# CLK_INPUT.net
KiCad netlist of a schematic drawn in Altium Designer
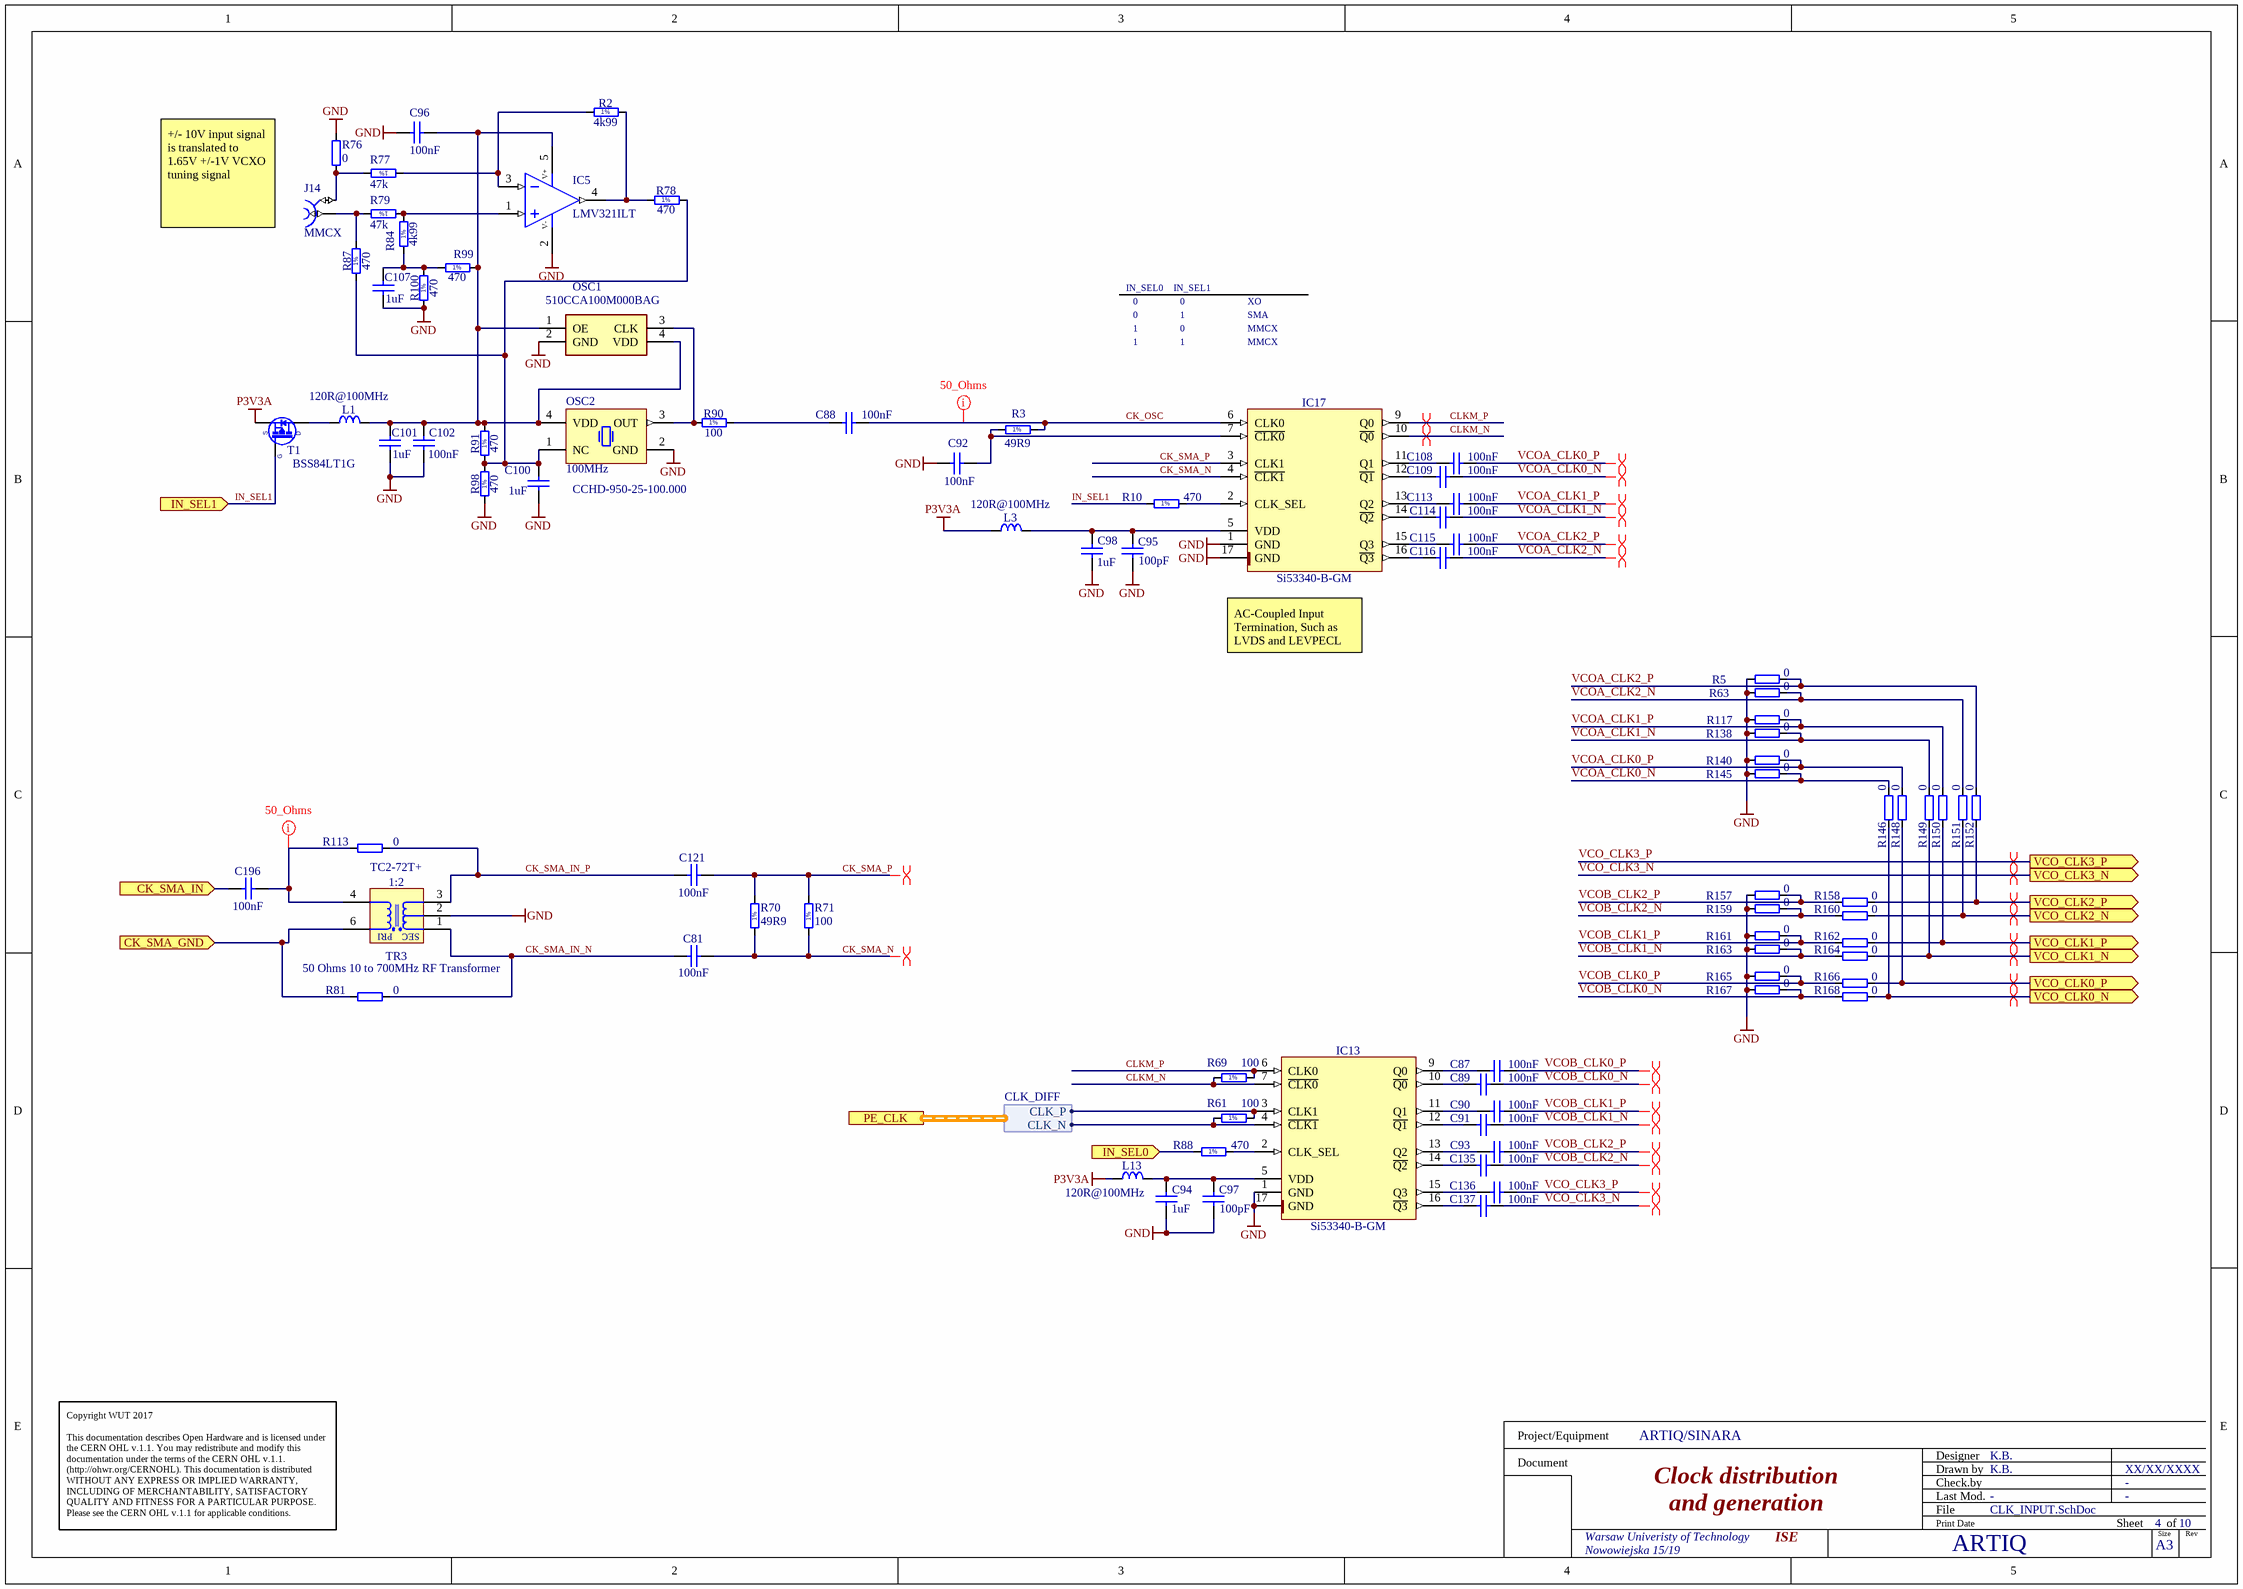
[diagram p0: CLK_INPUT.SchDoc]

(export (version "E")
  (design (tool "Eeschema 10.0.6"))
  (components
    (comp (ref "C81")
      (value "100nF")
      (footprint "CAPC1005X55N")
      (description "Non-polarised capacitor")
      (fields
        (field (name "PART NUMBER") "CC0402_100NF_16V_10%_X5R")
        (field (name "VOLTAGE") "16V")
        (field (name "AUTHOR") "CERN DEM JLC")
      )
      (libsource (lib "Capacitors") (part "Capacitor - non polarized"))
    )
    (comp (ref "C87")
      (value "100nF")
      (footprint "CAPC1005X55N")
      (description "Non-polarised capacitor")
      (fields
        (field (name "PART NUMBER") "CC0402_100NF_16V_10%_X5R")
        (field (name "VOLTAGE") "16V")
        (field (name "AUTHOR") "CERN DEM JLC")
      )
      (libsource (lib "Capacitors") (part "Capacitor - non polarized"))
    )
    (comp (ref "C88")
      (value "100nF")
      (footprint "CAPC1005X55N")
      (description "Non-polarised capacitor")
      (fields
        (field (name "PART NUMBER") "CC0402_100NF_16V_10%_X5R")
        (field (name "VOLTAGE") "16V")
        (field (name "AUTHOR") "CERN DEM JLC")
      )
      (libsource (lib "Capacitors") (part "Capacitor - non polarized"))
    )
    (comp (ref "C89")
      (value "100nF")
      (footprint "CAPC1005X55N")
      (description "Non-polarised capacitor")
      (fields
        (field (name "PART NUMBER") "CC0402_100NF_16V_10%_X5R")
        (field (name "VOLTAGE") "16V")
        (field (name "AUTHOR") "CERN DEM JLC")
      )
      (libsource (lib "Capacitors") (part "Capacitor - non polarized"))
    )
    (comp (ref "C90")
      (value "100nF")
      (footprint "CAPC1005X55N")
      (description "Non-polarised capacitor")
      (fields
        (field (name "PART NUMBER") "CC0402_100NF_16V_10%_X5R")
        (field (name "VOLTAGE") "16V")
        (field (name "AUTHOR") "CERN DEM JLC")
      )
      (libsource (lib "Capacitors") (part "Capacitor - non polarized"))
    )
    (comp (ref "C91")
      (value "100nF")
      (footprint "CAPC1005X55N")
      (description "Non-polarised capacitor")
      (fields
        (field (name "PART NUMBER") "CC0402_100NF_16V_10%_X5R")
        (field (name "VOLTAGE") "16V")
        (field (name "AUTHOR") "CERN DEM JLC")
      )
      (libsource (lib "Capacitors") (part "Capacitor - non polarized"))
    )
    (comp (ref "C92")
      (value "100nF")
      (footprint "CAPC1005X55N")
      (description "Non-polarised capacitor")
      (fields
        (field (name "PART NUMBER") "CC0402_100NF_16V_10%_X5R")
        (field (name "VOLTAGE") "16V")
        (field (name "AUTHOR") "CERN DEM JLC")
      )
      (libsource (lib "Capacitors") (part "Capacitor - non polarized"))
    )
    (comp (ref "C93")
      (value "100nF")
      (footprint "CAPC1005X55N")
      (description "Non-polarised capacitor")
      (fields
        (field (name "PART NUMBER") "CC0402_100NF_16V_10%_X5R")
        (field (name "VOLTAGE") "16V")
        (field (name "AUTHOR") "CERN DEM JLC")
      )
      (libsource (lib "Capacitors") (part "Capacitor - non polarized"))
    )
    (comp (ref "C94")
      (value "1uF")
      (footprint "CAPC1005X55N")
      (description "Non-polarised capacitor")
      (fields
        (field (name "PART NUMBER") "CC0402_1UF_16V_10%_X5R")
        (field (name "VOLTAGE") "16V")
        (field (name "AUTHOR") "CERN DEM JLC")
      )
      (libsource (lib "Capacitors") (part "Capacitor - non polarized"))
    )
    (comp (ref "C95")
      (value "100pF")
      (footprint "CAPC1005X55N")
      (description "Non-polarised capacitor")
      (fields
        (field (name "PART NUMBER") "CC0402_100PF_50V_5%_C0G")
        (field (name "VOLTAGE") "50V")
        (field (name "AUTHOR") "CERN DEM JLC")
      )
      (libsource (lib "Capacitors") (part "Capacitor - non polarized"))
    )
    (comp (ref "C96")
      (value "100nF")
      (footprint "CAPC1005X55N")
      (description "Non-polarised capacitor")
      (fields
        (field (name "PART NUMBER") "CC0402_100NF_16V_10%_X5R")
        (field (name "VOLTAGE") "16V")
        (field (name "AUTHOR") "CERN DEM JLC")
      )
      (libsource (lib "Capacitors") (part "Capacitor - non polarized"))
    )
    (comp (ref "C97")
      (value "100pF")
      (footprint "CAPC1005X55N")
      (description "Non-polarised capacitor")
      (fields
        (field (name "PART NUMBER") "CC0402_100PF_50V_5%_C0G")
        (field (name "VOLTAGE") "50V")
        (field (name "AUTHOR") "CERN DEM JLC")
      )
      (libsource (lib "Capacitors") (part "Capacitor - non polarized"))
    )
    (comp (ref "C98")
      (value "1uF")
      (footprint "CAPC1005X55N")
      (description "Non-polarised capacitor")
      (fields
        (field (name "PART NUMBER") "CC0402_1UF_16V_10%_X5R")
        (field (name "VOLTAGE") "16V")
        (field (name "AUTHOR") "CERN DEM JLC")
      )
      (libsource (lib "Capacitors") (part "Capacitor - non polarized"))
    )
    (comp (ref "C100")
      (value "1uF")
      (footprint "CAPC1005X55N")
      (description "Non-polarised capacitor")
      (fields
        (field (name "PART NUMBER") "CC0402_1UF_16V_10%_X5R")
        (field (name "VOLTAGE") "16V")
        (field (name "AUTHOR") "CERN DEM JLC")
      )
      (libsource (lib "Capacitors") (part "Capacitor - non polarized"))
    )
    (comp (ref "C101")
      (value "1uF")
      (footprint "CAPC1005X55N")
      (description "Non-polarised capacitor")
      (fields
        (field (name "PART NUMBER") "CC0402_1UF_16V_10%_X5R")
        (field (name "VOLTAGE") "16V")
        (field (name "AUTHOR") "CERN DEM JLC")
      )
      (libsource (lib "Capacitors") (part "Capacitor - non polarized"))
    )
    (comp (ref "C102")
      (value "100nF")
      (footprint "CAPC1005X55N")
      (description "Non-polarised capacitor")
      (fields
        (field (name "PART NUMBER") "CC0402_100NF_16V_10%_X5R")
        (field (name "VOLTAGE") "16V")
        (field (name "AUTHOR") "CERN DEM JLC")
      )
      (libsource (lib "Capacitors") (part "Capacitor - non polarized"))
    )
    (comp (ref "C107")
      (value "1uF")
      (footprint "CAPC1005X55N")
      (description "Non-polarised capacitor")
      (fields
        (field (name "PART NUMBER") "CC0402_1UF_16V_10%_X5R")
        (field (name "VOLTAGE") "16V")
        (field (name "AUTHOR") "CERN DEM JLC")
      )
      (libsource (lib "Capacitors") (part "Capacitor - non polarized"))
    )
    (comp (ref "C108")
      (value "100nF")
      (footprint "CAPC1005X55N")
      (description "Non-polarised capacitor")
      (fields
        (field (name "PART NUMBER") "CC0402_100NF_16V_10%_X5R")
        (field (name "VOLTAGE") "16V")
        (field (name "AUTHOR") "CERN DEM JLC")
      )
      (libsource (lib "Capacitors") (part "Capacitor - non polarized"))
    )
    (comp (ref "C109")
      (value "100nF")
      (footprint "CAPC1005X55N")
      (description "Non-polarised capacitor")
      (fields
        (field (name "PART NUMBER") "CC0402_100NF_16V_10%_X5R")
        (field (name "VOLTAGE") "16V")
        (field (name "AUTHOR") "CERN DEM JLC")
      )
      (libsource (lib "Capacitors") (part "Capacitor - non polarized"))
    )
    (comp (ref "C113")
      (value "100nF")
      (footprint "CAPC1005X55N")
      (description "Non-polarised capacitor")
      (fields
        (field (name "PART NUMBER") "CC0402_100NF_16V_10%_X5R")
        (field (name "VOLTAGE") "16V")
        (field (name "AUTHOR") "CERN DEM JLC")
      )
      (libsource (lib "Capacitors") (part "Capacitor - non polarized"))
    )
    (comp (ref "C114")
      (value "100nF")
      (footprint "CAPC1005X55N")
      (description "Non-polarised capacitor")
      (fields
        (field (name "PART NUMBER") "CC0402_100NF_16V_10%_X5R")
        (field (name "VOLTAGE") "16V")
        (field (name "AUTHOR") "CERN DEM JLC")
      )
      (libsource (lib "Capacitors") (part "Capacitor - non polarized"))
    )
    (comp (ref "C115")
      (value "100nF")
      (footprint "CAPC1005X55N")
      (description "Non-polarised capacitor")
      (fields
        (field (name "PART NUMBER") "CC0402_100NF_16V_10%_X5R")
        (field (name "VOLTAGE") "16V")
        (field (name "AUTHOR") "CERN DEM JLC")
      )
      (libsource (lib "Capacitors") (part "Capacitor - non polarized"))
    )
    (comp (ref "C116")
      (value "100nF")
      (footprint "CAPC1005X55N")
      (description "Non-polarised capacitor")
      (fields
        (field (name "PART NUMBER") "CC0402_100NF_16V_10%_X5R")
        (field (name "VOLTAGE") "16V")
        (field (name "AUTHOR") "CERN DEM JLC")
      )
      (libsource (lib "Capacitors") (part "Capacitor - non polarized"))
    )
    (comp (ref "C121")
      (value "100nF")
      (footprint "CAPC1005X55N")
      (description "Non-polarised capacitor")
      (fields
        (field (name "PART NUMBER") "CC0402_100NF_16V_10%_X5R")
        (field (name "VOLTAGE") "16V")
        (field (name "AUTHOR") "CERN DEM JLC")
      )
      (libsource (lib "Capacitors") (part "Capacitor - non polarized"))
    )
    (comp (ref "C135")
      (value "100nF")
      (footprint "CAPC1005X55N")
      (description "Non-polarised capacitor")
      (fields
        (field (name "PART NUMBER") "CC0402_100NF_16V_10%_X5R")
        (field (name "VOLTAGE") "16V")
        (field (name "AUTHOR") "CERN DEM JLC")
      )
      (libsource (lib "Capacitors") (part "Capacitor - non polarized"))
    )
    (comp (ref "C136")
      (value "100nF")
      (footprint "CAPC1005X55N")
      (description "Non-polarised capacitor")
      (fields
        (field (name "PART NUMBER") "CC0402_100NF_16V_10%_X5R")
        (field (name "VOLTAGE") "16V")
        (field (name "AUTHOR") "CERN DEM JLC")
      )
      (libsource (lib "Capacitors") (part "Capacitor - non polarized"))
    )
    (comp (ref "C137")
      (value "100nF")
      (footprint "CAPC1005X55N")
      (description "Non-polarised capacitor")
      (fields
        (field (name "PART NUMBER") "CC0402_100NF_16V_10%_X5R")
        (field (name "VOLTAGE") "16V")
        (field (name "AUTHOR") "CERN DEM JLC")
      )
      (libsource (lib "Capacitors") (part "Capacitor - non polarized"))
    )
    (comp (ref "C196")
      (value "100nF")
      (footprint "CAPC1005X55N")
      (description "Non-polarised capacitor")
      (fields
        (field (name "PART NUMBER") "CC0402_100NF_16V_10%_X5R")
        (field (name "VOLTAGE") "16V")
        (field (name "AUTHOR") "CERN DEM JLC")
      )
      (libsource (lib "Capacitors") (part "Capacitor - non polarized"))
    )
    (comp (ref "IC5")
      (value "LMV321ILT")
      (footprint "SOT95P280X145-5N")
      (description "Operational Amplifier")
      (fields (field (name "MANUFACTURER") "ST MICROELECTRONICS") (field (name "AUTHOR") "CERN DEM MR"))
      (libsource (lib "ICs And Semiconductors") (part "Operational Amplifier Type10"))
    )
    (comp (ref "IC13")
      (value "Si53340-B-GM")
      (footprint "QFN50P300X300X90-17N-S175")
      (description "Low-Jitter LVDS Fanout Clock Buffers, 10-Output,  Any-Input, Any-Frequency up to 1250MHz")
      (fields (field (name "MANUFACTURER") "SILICON LABS") (field (name "AUTHOR") "CERN DEM MR"))
      (libsource (lib "ICs And Semiconductors") (part "Si53340"))
    )
    (comp (ref "IC17")
      (value "Si53340-B-GM")
      (footprint "QFN50P300X300X90-17N-S175")
      (description "Low-Jitter LVDS Fanout Clock Buffers, 10-Output,  Any-Input, Any-Frequency up to 1250MHz")
      (fields (field (name "MANUFACTURER") "SILICON LABS") (field (name "AUTHOR") "CERN DEM MR"))
      (libsource (lib "ICs And Semiconductors") (part "Si53340"))
    )
    (comp (ref "J14")
      (value "MMCX")
      (footprint "SAMTEC_MMCX-J-P-H-ST-TH1")
      (fields
        (field (name "PART NUMBER") "SAMTEC_MMCX-J-P-H-ST-TH1")
        (field (name "MANUFACTURER") "SAMTEC")
        (field (name "MANUFACTURER PART NUMBER") "MMCX-J-P-H-ST-TH1")
        (field (name "AUTHOR") "CERN DEM JLC")
      )
      (libsource (lib "Connectors") (part "Coax_1Female_1Shield"))
    )
    (comp (ref "L1")
      (value "120R@100MHz")
      (footprint "INDC1608X95N")
      (description "Inductor")
      (fields
        (field (name "PART NUMBER") "IND0603_MURATA_BLM18PG121SN1D")
        (field (name "POWER") "2A")
        (field (name "AUTHOR") "CERN DEM BC")
      )
      (libsource (lib "Inductors & Transformers") (part "Inductor"))
    )
    (comp (ref "L3")
      (value "120R@100MHz")
      (footprint "INDC1608X95N")
      (description "Inductor")
      (fields
        (field (name "PART NUMBER") "IND0603_MURATA_BLM18PG121SN1D")
        (field (name "POWER") "2A")
        (field (name "AUTHOR") "CERN DEM BC")
      )
      (libsource (lib "Inductors & Transformers") (part "Inductor"))
    )
    (comp (ref "L13")
      (value "120R@100MHz")
      (footprint "INDC1608X95N")
      (description "Inductor")
      (fields
        (field (name "PART NUMBER") "IND0603_MURATA_BLM18PG121SN1D")
        (field (name "POWER") "2A")
        (field (name "AUTHOR") "CERN DEM BC")
      )
      (libsource (lib "Inductors & Transformers") (part "Inductor"))
    )
    (comp (ref "OSC1")
      (value "510CCA100M000BAG")
      (footprint "510CBA49M1520BAG")
      (description "Crystal or Oscillator")
      (fields (field (name "MOUSER PART NUMBER") "634-510CCA100M000BAG"))
      (libsource (lib "*") (part "510CCA100M000BAG"))
    )
    (comp (ref "OSC2")
      (value "100MHz")
      (footprint "OSC_CRYSTEK_CCHD-950")
      (description "100MHz low noise oscillator")
      (fields
        (field (name "PART NUMBER") "OSC_100MHZ_CRYSTEK_CCHD-950-25-100.000")
        (field (name "MANUFACTURER") "CRYSTEK CRYSTAL")
        (field (name "MANUFACTURER PART NUMBER") "CCHD-950-25-100.000")
        (field (name "AUTHOR") "GK")
      )
      (libsource (lib "LIBRARY_SCH") (part "OSC_CCHD-950"))
    )
    (comp (ref "R2")
      (value "4k99")
      (footprint "RESC1608X55N")
      (description "Resistor - 1%")
      (fields
        (field (name "PART NUMBER") "R0603_4K99_1%_0.063W_50PPM")
        (field (name "POWER") "0.063W")
        (field (name "AUTHOR") "CERN DEM JLC")
      )
      (libsource (lib "Resistors") (part "Resistor - 1%"))
    )
    (comp (ref "R3")
      (value "49R9")
      (footprint "RESC1005X40N")
      (description "Resistor - 1%")
      (fields
        (field (name "PART NUMBER") "R0402_49R9_1%_0.0625W_100PPM")
        (field (name "POWER") "0.0625W")
        (field (name "AUTHOR") "CERN DEM JLC")
      )
      (libsource (lib "Resistors") (part "Resistor - 1%"))
    )
    (comp (ref "R5")
      (value "0")
      (footprint "RESC1005X40N")
      (description "Resistor")
      (fields
        (field (name "PART NUMBER") "R0402_0R_JUMPER")
        (field (name "MANUFACTURER") "GENERIC")
        (field (name "AUTHOR") "CERN DEM JLC")
      )
      (libsource (lib "Resistors") (part "Resistor"))
    )
    (comp (ref "R10")
      (value "470")
      (footprint "RESC1005X40N")
      (description "Resistor - 1%")
      (fields
        (field (name "PART NUMBER") "R0402_470R_1%_0.0625W_100PPM")
        (field (name "POWER") "0.0625W")
        (field (name "AUTHOR") "CERN DEM JLC")
      )
      (libsource (lib "Resistors") (part "Resistor - 1%"))
    )
    (comp (ref "R61")
      (value "100")
      (footprint "RESC1005X40N")
      (description "Resistor - 1%")
      (fields
        (field (name "PART NUMBER") "R0402_100R_1%_0.0625W_100PPM")
        (field (name "POWER") "0.0625W")
        (field (name "AUTHOR") "CERN DEM JLC")
      )
      (libsource (lib "Resistors") (part "Resistor - 1%"))
    )
    (comp (ref "R63")
      (value "0")
      (footprint "RESC1005X40N")
      (description "Resistor")
      (fields
        (field (name "PART NUMBER") "R0402_0R_JUMPER")
        (field (name "MANUFACTURER") "GENERIC")
        (field (name "AUTHOR") "CERN DEM JLC")
      )
      (libsource (lib "Resistors") (part "Resistor"))
    )
    (comp (ref "R69")
      (value "100")
      (footprint "RESC1005X40N")
      (description "Resistor - 1%")
      (fields
        (field (name "PART NUMBER") "R0402_100R_1%_0.0625W_100PPM")
        (field (name "POWER") "0.0625W")
        (field (name "AUTHOR") "CERN DEM JLC")
      )
      (libsource (lib "Resistors") (part "Resistor - 1%"))
    )
    (comp (ref "R70")
      (value "49R9")
      (footprint "RESC1005X40N")
      (description "Resistor - 1%")
      (fields
        (field (name "PART NUMBER") "R0402_49R9_1%_0.0625W_100PPM")
        (field (name "POWER") "0.0625W")
        (field (name "AUTHOR") "CERN DEM JLC")
      )
      (libsource (lib "Resistors") (part "Resistor - 1%"))
    )
    (comp (ref "R71")
      (value "100")
      (footprint "RESC1005X40N")
      (description "Resistor - 1%")
      (fields
        (field (name "PART NUMBER") "R0402_100R_1%_0.0625W_100PPM")
        (field (name "POWER") "0.0625W")
        (field (name "AUTHOR") "CERN DEM JLC")
      )
      (libsource (lib "Resistors") (part "Resistor - 1%"))
    )
    (comp (ref "R76")
      (value "0")
      (footprint "RESC1005X40N")
      (description "Resistor")
      (fields
        (field (name "PART NUMBER") "R0402_0R_JUMPER")
        (field (name "MANUFACTURER") "GENERIC")
        (field (name "AUTHOR") "CERN DEM JLC")
      )
      (libsource (lib "Resistors") (part "Resistor"))
    )
    (comp (ref "R77")
      (value "47k")
      (footprint "RESC1608X55N")
      (description "Resistor - 1%")
      (fields
        (field (name "PART NUMBER") "R0603_47K_1%_0.1W_100PPM")
        (field (name "POWER") "0.1W")
        (field (name "AUTHOR") "CERN DEM JLC")
      )
      (libsource (lib "Resistors") (part "Resistor - 1%"))
    )
    (comp (ref "R78")
      (value "470")
      (footprint "RESC1608X55N")
      (description "Resistor - 1%")
      (fields
        (field (name "PART NUMBER") "R0603_470R_1%_0.1W_100PPM")
        (field (name "POWER") "0.1W")
        (field (name "AUTHOR") "CERN DEM JLC")
      )
      (libsource (lib "Resistors") (part "Resistor - 1%"))
    )
    (comp (ref "R79")
      (value "47k")
      (footprint "RESC1608X55N")
      (description "Resistor - 1%")
      (fields
        (field (name "PART NUMBER") "R0603_47K_1%_0.1W_100PPM")
        (field (name "POWER") "0.1W")
        (field (name "AUTHOR") "CERN DEM JLC")
      )
      (libsource (lib "Resistors") (part "Resistor - 1%"))
    )
    (comp (ref "R81")
      (value "0")
      (footprint "RESC1005X40N")
      (description "Resistor")
      (fields
        (field (name "PART NUMBER") "R0402_0R_JUMPER")
        (field (name "MANUFACTURER") "GENERIC")
        (field (name "AUTHOR") "CERN DEM JLC")
      )
      (libsource (lib "Resistors") (part "Resistor"))
    )
    (comp (ref "R84")
      (value "4k99")
      (footprint "RESC1608X55N")
      (description "Resistor - 1%")
      (fields
        (field (name "PART NUMBER") "R0603_4K99_1%_0.063W_50PPM")
        (field (name "POWER") "0.063W")
        (field (name "AUTHOR") "CERN DEM JLC")
      )
      (libsource (lib "Resistors") (part "Resistor - 1%"))
    )
    (comp (ref "R87")
      (value "470")
      (footprint "RESC1608X55N")
      (description "Resistor - 1%")
      (fields
        (field (name "PART NUMBER") "R0603_470R_1%_0.1W_100PPM")
        (field (name "POWER") "0.1W")
        (field (name "AUTHOR") "CERN DEM JLC")
      )
      (libsource (lib "Resistors") (part "Resistor - 1%"))
    )
    (comp (ref "R88")
      (value "470")
      (footprint "RESC1005X40N")
      (description "Resistor - 1%")
      (fields
        (field (name "PART NUMBER") "R0402_470R_1%_0.0625W_100PPM")
        (field (name "POWER") "0.0625W")
        (field (name "AUTHOR") "CERN DEM JLC")
      )
      (libsource (lib "Resistors") (part "Resistor - 1%"))
    )
    (comp (ref "R90")
      (value "100")
      (footprint "RESC1005X40N")
      (description "Resistor - 1%")
      (fields
        (field (name "PART NUMBER") "R0402_100R_1%_0.0625W_100PPM")
        (field (name "POWER") "0.0625W")
        (field (name "AUTHOR") "CERN DEM JLC")
      )
      (libsource (lib "Resistors") (part "Resistor - 1%"))
    )
    (comp (ref "R91")
      (value "470")
      (footprint "RESC1608X55N")
      (description "Resistor - 1%")
      (fields
        (field (name "PART NUMBER") "R0603_470R_1%_0.1W_100PPM")
        (field (name "POWER") "0.1W")
        (field (name "AUTHOR") "CERN DEM JLC")
      )
      (libsource (lib "Resistors") (part "Resistor - 1%"))
    )
    (comp (ref "R98")
      (value "470")
      (footprint "RESC1608X55N")
      (description "Resistor - 1%")
      (fields
        (field (name "PART NUMBER") "R0603_470R_1%_0.1W_100PPM")
        (field (name "POWER") "0.1W")
        (field (name "AUTHOR") "CERN DEM JLC")
      )
      (libsource (lib "Resistors") (part "Resistor - 1%"))
    )
    (comp (ref "R99")
      (value "470")
      (footprint "RESC1608X55N")
      (description "Resistor - 1%")
      (fields
        (field (name "PART NUMBER") "R0603_470R_1%_0.1W_100PPM")
        (field (name "POWER") "0.1W")
        (field (name "AUTHOR") "CERN DEM JLC")
      )
      (libsource (lib "Resistors") (part "Resistor - 1%"))
    )
    (comp (ref "R100")
      (value "470")
      (footprint "RESC1608X55N")
      (description "Resistor - 1%")
      (fields
        (field (name "PART NUMBER") "R0603_470R_1%_0.1W_100PPM")
        (field (name "POWER") "0.1W")
        (field (name "AUTHOR") "CERN DEM JLC")
      )
      (libsource (lib "Resistors") (part "Resistor - 1%"))
    )
    (comp (ref "R113")
      (value "0")
      (footprint "RESC1005X40N")
      (description "Resistor")
      (fields
        (field (name "PART NUMBER") "R0402_0R_JUMPER")
        (field (name "MANUFACTURER") "GENERIC")
        (field (name "AUTHOR") "CERN DEM JLC")
      )
      (libsource (lib "Resistors") (part "Resistor"))
    )
    (comp (ref "R117")
      (value "0")
      (footprint "RESC1005X40N")
      (description "Resistor")
      (fields
        (field (name "PART NUMBER") "R0402_0R_JUMPER")
        (field (name "MANUFACTURER") "GENERIC")
        (field (name "AUTHOR") "CERN DEM JLC")
      )
      (libsource (lib "Resistors") (part "Resistor"))
    )
    (comp (ref "R138")
      (value "0")
      (footprint "RESC1005X40N")
      (description "Resistor")
      (fields
        (field (name "PART NUMBER") "R0402_0R_JUMPER")
        (field (name "MANUFACTURER") "GENERIC")
        (field (name "AUTHOR") "CERN DEM JLC")
      )
      (libsource (lib "Resistors") (part "Resistor"))
    )
    (comp (ref "R140")
      (value "0")
      (footprint "RESC1005X40N")
      (description "Resistor")
      (fields
        (field (name "PART NUMBER") "R0402_0R_JUMPER")
        (field (name "MANUFACTURER") "GENERIC")
        (field (name "AUTHOR") "CERN DEM JLC")
      )
      (libsource (lib "Resistors") (part "Resistor"))
    )
    (comp (ref "R145")
      (value "0")
      (footprint "RESC1005X40N")
      (description "Resistor")
      (fields
        (field (name "PART NUMBER") "R0402_0R_JUMPER")
        (field (name "MANUFACTURER") "GENERIC")
        (field (name "AUTHOR") "CERN DEM JLC")
      )
      (libsource (lib "Resistors") (part "Resistor"))
    )
    (comp (ref "R146")
      (value "0")
      (footprint "RESC1005X40N")
      (description "Resistor")
      (fields
        (field (name "PART NUMBER") "R0402_0R_JUMPER")
        (field (name "MANUFACTURER") "GENERIC")
        (field (name "AUTHOR") "CERN DEM JLC")
      )
      (libsource (lib "Resistors") (part "Resistor"))
    )
    (comp (ref "R148")
      (value "0")
      (footprint "RESC1005X40N")
      (description "Resistor")
      (fields
        (field (name "PART NUMBER") "R0402_0R_JUMPER")
        (field (name "MANUFACTURER") "GENERIC")
        (field (name "AUTHOR") "CERN DEM JLC")
      )
      (libsource (lib "Resistors") (part "Resistor"))
    )
    (comp (ref "R149")
      (value "0")
      (footprint "RESC1005X40N")
      (description "Resistor")
      (fields
        (field (name "PART NUMBER") "R0402_0R_JUMPER")
        (field (name "MANUFACTURER") "GENERIC")
        (field (name "AUTHOR") "CERN DEM JLC")
      )
      (libsource (lib "Resistors") (part "Resistor"))
    )
    (comp (ref "R150")
      (value "0")
      (footprint "RESC1005X40N")
      (description "Resistor")
      (fields
        (field (name "PART NUMBER") "R0402_0R_JUMPER")
        (field (name "MANUFACTURER") "GENERIC")
        (field (name "AUTHOR") "CERN DEM JLC")
      )
      (libsource (lib "Resistors") (part "Resistor"))
    )
    (comp (ref "R151")
      (value "0")
      (footprint "RESC1005X40N")
      (description "Resistor")
      (fields
        (field (name "PART NUMBER") "R0402_0R_JUMPER")
        (field (name "MANUFACTURER") "GENERIC")
        (field (name "AUTHOR") "CERN DEM JLC")
      )
      (libsource (lib "Resistors") (part "Resistor"))
    )
    (comp (ref "R152")
      (value "0")
      (footprint "RESC1005X40N")
      (description "Resistor")
      (fields
        (field (name "PART NUMBER") "R0402_0R_JUMPER")
        (field (name "MANUFACTURER") "GENERIC")
        (field (name "AUTHOR") "CERN DEM JLC")
      )
      (libsource (lib "Resistors") (part "Resistor"))
    )
    (comp (ref "R157")
      (value "0")
      (footprint "RESC1005X40N")
      (description "Resistor")
      (fields
        (field (name "PART NUMBER") "R0402_0R_JUMPER")
        (field (name "MANUFACTURER") "GENERIC")
        (field (name "AUTHOR") "CERN DEM JLC")
      )
      (libsource (lib "Resistors") (part "Resistor"))
    )
    (comp (ref "R158")
      (value "0")
      (footprint "RESC1005X40N")
      (description "Resistor")
      (fields
        (field (name "PART NUMBER") "R0402_0R_JUMPER")
        (field (name "MANUFACTURER") "GENERIC")
        (field (name "AUTHOR") "CERN DEM JLC")
      )
      (libsource (lib "Resistors") (part "Resistor"))
    )
    (comp (ref "R159")
      (value "0")
      (footprint "RESC1005X40N")
      (description "Resistor")
      (fields
        (field (name "PART NUMBER") "R0402_0R_JUMPER")
        (field (name "MANUFACTURER") "GENERIC")
        (field (name "AUTHOR") "CERN DEM JLC")
      )
      (libsource (lib "Resistors") (part "Resistor"))
    )
    (comp (ref "R160")
      (value "0")
      (footprint "RESC1005X40N")
      (description "Resistor")
      (fields
        (field (name "PART NUMBER") "R0402_0R_JUMPER")
        (field (name "MANUFACTURER") "GENERIC")
        (field (name "AUTHOR") "CERN DEM JLC")
      )
      (libsource (lib "Resistors") (part "Resistor"))
    )
    (comp (ref "R161")
      (value "0")
      (footprint "RESC1005X40N")
      (description "Resistor")
      (fields
        (field (name "PART NUMBER") "R0402_0R_JUMPER")
        (field (name "MANUFACTURER") "GENERIC")
        (field (name "AUTHOR") "CERN DEM JLC")
      )
      (libsource (lib "Resistors") (part "Resistor"))
    )
    (comp (ref "R162")
      (value "0")
      (footprint "RESC1005X40N")
      (description "Resistor")
      (fields
        (field (name "PART NUMBER") "R0402_0R_JUMPER")
        (field (name "MANUFACTURER") "GENERIC")
        (field (name "AUTHOR") "CERN DEM JLC")
      )
      (libsource (lib "Resistors") (part "Resistor"))
    )
    (comp (ref "R163")
      (value "0")
      (footprint "RESC1005X40N")
      (description "Resistor")
      (fields
        (field (name "PART NUMBER") "R0402_0R_JUMPER")
        (field (name "MANUFACTURER") "GENERIC")
        (field (name "AUTHOR") "CERN DEM JLC")
      )
      (libsource (lib "Resistors") (part "Resistor"))
    )
    (comp (ref "R164")
      (value "0")
      (footprint "RESC1005X40N")
      (description "Resistor")
      (fields
        (field (name "PART NUMBER") "R0402_0R_JUMPER")
        (field (name "MANUFACTURER") "GENERIC")
        (field (name "AUTHOR") "CERN DEM JLC")
      )
      (libsource (lib "Resistors") (part "Resistor"))
    )
    (comp (ref "R165")
      (value "0")
      (footprint "RESC1005X40N")
      (description "Resistor")
      (fields
        (field (name "PART NUMBER") "R0402_0R_JUMPER")
        (field (name "MANUFACTURER") "GENERIC")
        (field (name "AUTHOR") "CERN DEM JLC")
      )
      (libsource (lib "Resistors") (part "Resistor"))
    )
    (comp (ref "R166")
      (value "0")
      (footprint "RESC1005X40N")
      (description "Resistor")
      (fields
        (field (name "PART NUMBER") "R0402_0R_JUMPER")
        (field (name "MANUFACTURER") "GENERIC")
        (field (name "AUTHOR") "CERN DEM JLC")
      )
      (libsource (lib "Resistors") (part "Resistor"))
    )
    (comp (ref "R167")
      (value "0")
      (footprint "RESC1005X40N")
      (description "Resistor")
      (fields
        (field (name "PART NUMBER") "R0402_0R_JUMPER")
        (field (name "MANUFACTURER") "GENERIC")
        (field (name "AUTHOR") "CERN DEM JLC")
      )
      (libsource (lib "Resistors") (part "Resistor"))
    )
    (comp (ref "R168")
      (value "0")
      (footprint "RESC1005X40N")
      (description "Resistor")
      (fields
        (field (name "PART NUMBER") "R0402_0R_JUMPER")
        (field (name "MANUFACTURER") "GENERIC")
        (field (name "AUTHOR") "CERN DEM JLC")
      )
      (libsource (lib "Resistors") (part "Resistor"))
    )
    (comp (ref "T1")
      (value "BSS84LT1G")
      (footprint "SOT95P240X110-3N")
      (description "P-CHANNEL MOSFET WITH DIODE")
      (fields (field (name "MANUFACTURER") "ON SEMICONDUCTOR") (field (name "AUTHOR") "CERN DEM JLC"))
      (libsource (lib "ICs And Semiconductors") (part "P-MOSFET-D 1G 2S 3D"))
    )
    (comp (ref "TR3")
      (value "1:2")
      (footprint "XFMR_MINI-CIRCUITS_AT1521")
      (description "50 Ohms 10 to 700 MHzz RF Transformer")
      (fields
        (field (name "MANUFACTURER") "MINI-CIRCUITS")
        (field (name "MANUFACTURER PART NUMBER") "TC2-72T+")
        (field (name "PART NUMBER") "XFMR_MINI-CIRCUITS_TC2-72T+")
        (field (name "PART DESCRIPTION") "50 Ohms 10 to 700MHz RF Transformer")
        (field (name "AUTHOR") "GK")
      )
      (libsource (lib "Inductors_Transformers") (part "XFMR_MINI-CIRCUITS_TC2-72T+"))
    )
  )
  (nets
    (net (code "2") (name "/CK_OSC") (class "Default")
      (node (ref "C88") (pin "2") (pinfunction "2_2") (pintype "passive"))
      (node (ref "IC17") (pin "6") (pinfunction "CLK0_6") (pintype "input"))
      (node (ref "R3") (pin "2") (pinfunction "2_2") (pintype "passive"))
    )
    (net (code "3") (name "/CK_SMA_GND") (class "Default")
      (node (ref "R81") (pin "1") (pinfunction "1_1") (pintype "passive"))
      (node (ref "TR3") (pin "6") (pinfunction "PDOT_6") (pintype "passive"))
    )
    (net (code "4") (name "/CK_SMA_IN") (class "Default")
      (node (ref "C196") (pin "1") (pinfunction "1_1") (pintype "passive"))
    )
    (net (code "5") (name "/CK_SMA_IN_N") (class "Default")
      (node (ref "C81") (pin "1") (pinfunction "1_1") (pintype "passive"))
      (node (ref "R81") (pin "2") (pinfunction "2_2") (pintype "passive"))
      (node (ref "TR3") (pin "1") (pinfunction "SDOT_1") (pintype "passive"))
    )
    (net (code "6") (name "/CK_SMA_IN_P") (class "Default")
      (node (ref "C121") (pin "1") (pinfunction "1_1") (pintype "passive"))
      (node (ref "R113") (pin "2") (pinfunction "2_2") (pintype "passive"))
      (node (ref "TR3") (pin "3") (pinfunction "S_3") (pintype "passive"))
    )
    (net (code "7") (name "/CK_SMA_N") (class "Default")
      (node (ref "C81") (pin "2") (pinfunction "2_2") (pintype "passive"))
      (node (ref "IC17") (pin "4") (pinfunction "~{CLK1}_4") (pintype "input"))
      (node (ref "R70") (pin "1") (pinfunction "1_1") (pintype "passive"))
      (node (ref "R71") (pin "1") (pinfunction "1_1") (pintype "passive"))
    )
    (net (code "8") (name "/CK_SMA_P") (class "Default")
      (node (ref "C121") (pin "2") (pinfunction "2_2") (pintype "passive"))
      (node (ref "IC17") (pin "3") (pinfunction "CLK1_3") (pintype "input"))
      (node (ref "R70") (pin "2") (pinfunction "2_2") (pintype "passive"))
      (node (ref "R71") (pin "2") (pinfunction "2_2") (pintype "passive"))
    )
    (net (code "9") (name "/CLKM_N") (class "Default")
      (node (ref "IC13") (pin "7") (pinfunction "~{CLK0}_7") (pintype "input"))
      (node (ref "IC17") (pin "10") (pinfunction "~{Q0}_10") (pintype "output"))
      (node (ref "R69") (pin "1") (pinfunction "1_1") (pintype "passive"))
    )
    (net (code "10") (name "/CLKM_P") (class "Default")
      (node (ref "IC13") (pin "6") (pinfunction "CLK0_6") (pintype "input"))
      (node (ref "IC17") (pin "9") (pinfunction "Q0_9") (pintype "output"))
      (node (ref "R69") (pin "2") (pinfunction "2_2") (pintype "passive"))
    )
    (net (code "11") (name "/IN_SEL0") (class "Default")
      (node (ref "R88") (pin "1") (pinfunction "1_1") (pintype "passive"))
    )
    (net (code "12") (name "/IN_SEL1") (class "Default")
      (node (ref "R10") (pin "1") (pinfunction "1_1") (pintype "passive"))
      (node (ref "T1") (pin "1") (pinfunction "G_1") (pintype "passive"))
    )
    (net (code "13") (name "/VCOA_CLK0_N") (class "Default")
      (node (ref "C109") (pin "1") (pinfunction "1_1") (pintype "passive"))
      (node (ref "R145") (pin "2") (pinfunction "2_2") (pintype "passive"))
      (node (ref "R146") (pin "2") (pinfunction "2_2") (pintype "passive"))
    )
    (net (code "14") (name "/VCOA_CLK0_P") (class "Default")
      (node (ref "C108") (pin "1") (pinfunction "1_1") (pintype "passive"))
      (node (ref "R140") (pin "2") (pinfunction "2_2") (pintype "passive"))
      (node (ref "R148") (pin "2") (pinfunction "2_2") (pintype "passive"))
    )
    (net (code "15") (name "/VCOA_CLK1_N") (class "Default")
      (node (ref "C114") (pin "1") (pinfunction "1_1") (pintype "passive"))
      (node (ref "R138") (pin "2") (pinfunction "2_2") (pintype "passive"))
      (node (ref "R149") (pin "2") (pinfunction "2_2") (pintype "passive"))
    )
    (net (code "16") (name "/VCOA_CLK1_P") (class "Default")
      (node (ref "C113") (pin "1") (pinfunction "1_1") (pintype "passive"))
      (node (ref "R117") (pin "2") (pinfunction "2_2") (pintype "passive"))
      (node (ref "R150") (pin "2") (pinfunction "2_2") (pintype "passive"))
    )
    (net (code "17") (name "/VCOA_CLK2_N") (class "Default")
      (node (ref "C116") (pin "1") (pinfunction "1_1") (pintype "passive"))
      (node (ref "R151") (pin "2") (pinfunction "2_2") (pintype "passive"))
      (node (ref "R63") (pin "2") (pinfunction "2_2") (pintype "passive"))
    )
    (net (code "18") (name "/VCOA_CLK2_P") (class "Default")
      (node (ref "C115") (pin "1") (pinfunction "1_1") (pintype "passive"))
      (node (ref "R152") (pin "2") (pinfunction "2_2") (pintype "passive"))
      (node (ref "R5") (pin "2") (pinfunction "2_2") (pintype "passive"))
    )
    (net (code "19") (name "/VCOB_CLK0_N") (class "Default")
      (node (ref "C89") (pin "1") (pinfunction "1_1") (pintype "passive"))
      (node (ref "R167") (pin "2") (pinfunction "2_2") (pintype "passive"))
      (node (ref "R168") (pin "1") (pinfunction "1_1") (pintype "passive"))
    )
    (net (code "20") (name "/VCOB_CLK0_P") (class "Default")
      (node (ref "C87") (pin "1") (pinfunction "1_1") (pintype "passive"))
      (node (ref "R165") (pin "2") (pinfunction "2_2") (pintype "passive"))
      (node (ref "R166") (pin "1") (pinfunction "1_1") (pintype "passive"))
    )
    (net (code "21") (name "/VCOB_CLK1_N") (class "Default")
      (node (ref "C91") (pin "1") (pinfunction "1_1") (pintype "passive"))
      (node (ref "R163") (pin "2") (pinfunction "2_2") (pintype "passive"))
      (node (ref "R164") (pin "1") (pinfunction "1_1") (pintype "passive"))
    )
    (net (code "22") (name "/VCOB_CLK1_P") (class "Default")
      (node (ref "C90") (pin "1") (pinfunction "1_1") (pintype "passive"))
      (node (ref "R161") (pin "2") (pinfunction "2_2") (pintype "passive"))
      (node (ref "R162") (pin "1") (pinfunction "1_1") (pintype "passive"))
    )
    (net (code "23") (name "/VCOB_CLK2_N") (class "Default")
      (node (ref "C135") (pin "1") (pinfunction "1_1") (pintype "passive"))
      (node (ref "R159") (pin "2") (pinfunction "2_2") (pintype "passive"))
      (node (ref "R160") (pin "1") (pinfunction "1_1") (pintype "passive"))
    )
    (net (code "24") (name "/VCOB_CLK2_P") (class "Default")
      (node (ref "C93") (pin "1") (pinfunction "1_1") (pintype "passive"))
      (node (ref "R157") (pin "2") (pinfunction "2_2") (pintype "passive"))
      (node (ref "R158") (pin "1") (pinfunction "1_1") (pintype "passive"))
    )
    (net (code "25") (name "/VCO_CLK0_N") (class "Default")
      (node (ref "R146") (pin "1") (pinfunction "1_1") (pintype "passive"))
      (node (ref "R168") (pin "2") (pinfunction "2_2") (pintype "passive"))
    )
    (net (code "26") (name "/VCO_CLK0_P") (class "Default")
      (node (ref "R148") (pin "1") (pinfunction "1_1") (pintype "passive"))
      (node (ref "R166") (pin "2") (pinfunction "2_2") (pintype "passive"))
    )
    (net (code "27") (name "/VCO_CLK1_N") (class "Default")
      (node (ref "R149") (pin "1") (pinfunction "1_1") (pintype "passive"))
      (node (ref "R164") (pin "2") (pinfunction "2_2") (pintype "passive"))
    )
    (net (code "28") (name "/VCO_CLK1_P") (class "Default")
      (node (ref "R150") (pin "1") (pinfunction "1_1") (pintype "passive"))
      (node (ref "R162") (pin "2") (pinfunction "2_2") (pintype "passive"))
    )
    (net (code "29") (name "/VCO_CLK2_N") (class "Default")
      (node (ref "R151") (pin "1") (pinfunction "1_1") (pintype "passive"))
      (node (ref "R160") (pin "2") (pinfunction "2_2") (pintype "passive"))
    )
    (net (code "30") (name "/VCO_CLK2_P") (class "Default")
      (node (ref "R152") (pin "1") (pinfunction "1_1") (pintype "passive"))
      (node (ref "R158") (pin "2") (pinfunction "2_2") (pintype "passive"))
    )
    (net (code "31") (name "/VCO_CLK3_N") (class "Default")
      (node (ref "C137") (pin "1") (pinfunction "1_1") (pintype "passive"))
    )
    (net (code "32") (name "/VCO_CLK3_P") (class "Default")
      (node (ref "C136") (pin "1") (pinfunction "1_1") (pintype "passive"))
    )
    (net (code "34") (name "GND") (class "Default")
      (node (ref "C100") (pin "1") (pinfunction "1_1") (pintype "passive"))
      (node (ref "C101") (pin "1") (pinfunction "1_1") (pintype "passive"))
      (node (ref "C102") (pin "1") (pinfunction "1_1") (pintype "passive"))
      (node (ref "C107") (pin "1") (pinfunction "1_1") (pintype "passive"))
      (node (ref "C92") (pin "1") (pinfunction "1_1") (pintype "passive"))
      (node (ref "C94") (pin "1") (pinfunction "1_1") (pintype "passive"))
      (node (ref "C95") (pin "1") (pinfunction "1_1") (pintype "passive"))
      (node (ref "C96") (pin "1") (pinfunction "1_1") (pintype "passive"))
      (node (ref "C97") (pin "1") (pinfunction "1_1") (pintype "passive"))
      (node (ref "C98") (pin "1") (pinfunction "1_1") (pintype "passive"))
      (node (ref "IC13") (pin "1") (pinfunction "GND_1") (pintype "power_in"))
      (node (ref "IC13") (pin "17") (pinfunction "GND_17") (pintype "power_in"))
      (node (ref "IC17") (pin "1") (pinfunction "GND_1") (pintype "power_in"))
      (node (ref "IC17") (pin "17") (pinfunction "GND_17") (pintype "power_in"))
      (node (ref "IC5") (pin "2") (pinfunction "V-_2") (pintype "power_in"))
      (node (ref "OSC1") (pin "2") (pinfunction "GND_2") (pintype "passive"))
      (node (ref "OSC2") (pin "2") (pinfunction "GND_2") (pintype "power_in"))
      (node (ref "R100") (pin "1") (pinfunction "1_1") (pintype "passive"))
      (node (ref "R117") (pin "1") (pinfunction "1_1") (pintype "passive"))
      (node (ref "R138") (pin "1") (pinfunction "1_1") (pintype "passive"))
      (node (ref "R140") (pin "1") (pinfunction "1_1") (pintype "passive"))
      (node (ref "R145") (pin "1") (pinfunction "1_1") (pintype "passive"))
      (node (ref "R157") (pin "1") (pinfunction "1_1") (pintype "passive"))
      (node (ref "R159") (pin "1") (pinfunction "1_1") (pintype "passive"))
      (node (ref "R161") (pin "1") (pinfunction "1_1") (pintype "passive"))
      (node (ref "R163") (pin "1") (pinfunction "1_1") (pintype "passive"))
      (node (ref "R165") (pin "1") (pinfunction "1_1") (pintype "passive"))
      (node (ref "R167") (pin "1") (pinfunction "1_1") (pintype "passive"))
      (node (ref "R5") (pin "1") (pinfunction "1_1") (pintype "passive"))
      (node (ref "R63") (pin "1") (pinfunction "1_1") (pintype "passive"))
      (node (ref "R76") (pin "2") (pinfunction "2_2") (pintype "passive"))
      (node (ref "R98") (pin "1") (pinfunction "1_1") (pintype "passive"))
      (node (ref "TR3") (pin "2") (pinfunction "NC_2") (pintype "passive"))
    )
    (net (code "35") (name "Net-(C88-Pad1)") (class "Default")
      (node (ref "C88") (pin "1") (pinfunction "1_1") (pintype "passive"))
      (node (ref "R90") (pin "2") (pinfunction "2_2") (pintype "passive"))
    )
    (net (code "36") (name "Net-(C107-Pad2)") (class "Default")
      (node (ref "C107") (pin "2") (pinfunction "2_2") (pintype "passive"))
      (node (ref "R100") (pin "2") (pinfunction "2_2") (pintype "passive"))
      (node (ref "R84") (pin "1") (pinfunction "1_1") (pintype "passive"))
      (node (ref "R99") (pin "1") (pinfunction "1_1") (pintype "passive"))
    )
    (net (code "37") (name "Net-(IC5-IN+)") (class "Default")
      (node (ref "IC5") (pin "1") (pinfunction "IN+_1") (pintype "input"))
      (node (ref "R79") (pin "1") (pinfunction "1_1") (pintype "passive"))
      (node (ref "R84") (pin "2") (pinfunction "2_2") (pintype "passive"))
    )
    (net (code "38") (name "Net-(IC5-IN-)") (class "Default")
      (node (ref "IC5") (pin "3") (pinfunction "IN-_3") (pintype "input"))
      (node (ref "R2") (pin "1") (pinfunction "1_1") (pintype "passive"))
      (node (ref "R77") (pin "1") (pinfunction "1_1") (pintype "passive"))
    )
    (net (code "39") (name "Net-(IC5-OUT)") (class "Default")
      (node (ref "IC5") (pin "4") (pinfunction "OUT_4") (pintype "output"))
      (node (ref "R2") (pin "2") (pinfunction "2_2") (pintype "passive"))
      (node (ref "R78") (pin "1") (pinfunction "1_1") (pintype "passive"))
    )
    (net (code "40") (name "Net-(IC5-V+)") (class "Default")
      (node (ref "C101") (pin "2") (pinfunction "2_2") (pintype "passive"))
      (node (ref "C102") (pin "2") (pinfunction "2_2") (pintype "passive"))
      (node (ref "C96") (pin "2") (pinfunction "2_2") (pintype "passive"))
      (node (ref "IC5") (pin "5") (pinfunction "V+_5") (pintype "power_in"))
      (node (ref "L1") (pin "1") (pinfunction "1_1") (pintype "passive"))
      (node (ref "OSC1") (pin "1") (pinfunction "OE_1") (pintype "passive"))
      (node (ref "OSC1") (pin "4") (pinfunction "VDD_4") (pintype "passive"))
      (node (ref "OSC2") (pin "4") (pinfunction "VDD_4") (pintype "power_in"))
      (node (ref "R91") (pin "2") (pinfunction "2_2") (pintype "passive"))
      (node (ref "R99") (pin "2") (pinfunction "2_2") (pintype "passive"))
    )
    (net (code "41") (name "Net-(IC13-CLK1)") (class "Default")
      (node (ref "IC13") (pin "3") (pinfunction "CLK1_3") (pintype "input"))
      (node (ref "R61") (pin "2") (pinfunction "2_2") (pintype "passive"))
    )
    (net (code "42") (name "Net-(IC13-CLK_SEL)") (class "Default")
      (node (ref "IC13") (pin "2") (pinfunction "CLK_SEL_2") (pintype "input"))
      (node (ref "R88") (pin "2") (pinfunction "2_2") (pintype "passive"))
    )
    (net (code "43") (name "Net-(IC13-Q0)") (class "Default")
      (node (ref "C87") (pin "2") (pinfunction "2_2") (pintype "passive"))
      (node (ref "IC13") (pin "9") (pinfunction "Q0_9") (pintype "output"))
    )
    (net (code "44") (name "Net-(IC13-Q1)") (class "Default")
      (node (ref "C90") (pin "2") (pinfunction "2_2") (pintype "passive"))
      (node (ref "IC13") (pin "11") (pinfunction "Q1_11") (pintype "output"))
    )
    (net (code "45") (name "Net-(IC13-Q2)") (class "Default")
      (node (ref "C93") (pin "2") (pinfunction "2_2") (pintype "passive"))
      (node (ref "IC13") (pin "13") (pinfunction "Q2_13") (pintype "output"))
    )
    (net (code "46") (name "Net-(IC13-Q3)") (class "Default")
      (node (ref "C136") (pin "2") (pinfunction "2_2") (pintype "passive"))
      (node (ref "IC13") (pin "15") (pinfunction "Q3_15") (pintype "output"))
    )
    (net (code "47") (name "Net-(IC13-VDD)") (class "Default")
      (node (ref "C94") (pin "2") (pinfunction "2_2") (pintype "passive"))
      (node (ref "C97") (pin "2") (pinfunction "2_2") (pintype "passive"))
      (node (ref "IC13") (pin "5") (pinfunction "VDD_5") (pintype "power_in"))
      (node (ref "L13") (pin "1") (pinfunction "1_1") (pintype "passive"))
    )
    (net (code "48") (name "Net-(IC13-~{CLK1})") (class "Default")
      (node (ref "IC13") (pin "4") (pinfunction "~{CLK1}_4") (pintype "input"))
      (node (ref "R61") (pin "1") (pinfunction "1_1") (pintype "passive"))
    )
    (net (code "49") (name "Net-(IC13-~{Q0})") (class "Default")
      (node (ref "C89") (pin "2") (pinfunction "2_2") (pintype "passive"))
      (node (ref "IC13") (pin "10") (pinfunction "~{Q0}_10") (pintype "output"))
    )
    (net (code "50") (name "Net-(IC13-~{Q1})") (class "Default")
      (node (ref "C91") (pin "2") (pinfunction "2_2") (pintype "passive"))
      (node (ref "IC13") (pin "12") (pinfunction "~{Q1}_12") (pintype "output"))
    )
    (net (code "51") (name "Net-(IC13-~{Q2})") (class "Default")
      (node (ref "C135") (pin "2") (pinfunction "2_2") (pintype "passive"))
      (node (ref "IC13") (pin "14") (pinfunction "~{Q2}_14") (pintype "output"))
    )
    (net (code "52") (name "Net-(IC13-~{Q3})") (class "Default")
      (node (ref "C137") (pin "2") (pinfunction "2_2") (pintype "passive"))
      (node (ref "IC13") (pin "16") (pinfunction "~{Q3}_16") (pintype "output"))
    )
    (net (code "53") (name "Net-(IC17-CLK_SEL)") (class "Default")
      (node (ref "IC17") (pin "2") (pinfunction "CLK_SEL_2") (pintype "input"))
      (node (ref "R10") (pin "2") (pinfunction "2_2") (pintype "passive"))
    )
    (net (code "54") (name "Net-(IC17-Q1)") (class "Default")
      (node (ref "C108") (pin "2") (pinfunction "2_2") (pintype "passive"))
      (node (ref "IC17") (pin "11") (pinfunction "Q1_11") (pintype "output"))
    )
    (net (code "55") (name "Net-(IC17-Q2)") (class "Default")
      (node (ref "C113") (pin "2") (pinfunction "2_2") (pintype "passive"))
      (node (ref "IC17") (pin "13") (pinfunction "Q2_13") (pintype "output"))
    )
    (net (code "56") (name "Net-(IC17-Q3)") (class "Default")
      (node (ref "C115") (pin "2") (pinfunction "2_2") (pintype "passive"))
      (node (ref "IC17") (pin "15") (pinfunction "Q3_15") (pintype "output"))
    )
    (net (code "57") (name "Net-(IC17-VDD)") (class "Default")
      (node (ref "C95") (pin "2") (pinfunction "2_2") (pintype "passive"))
      (node (ref "C98") (pin "2") (pinfunction "2_2") (pintype "passive"))
      (node (ref "IC17") (pin "5") (pinfunction "VDD_5") (pintype "power_in"))
      (node (ref "L3") (pin "1") (pinfunction "1_1") (pintype "passive"))
    )
    (net (code "58") (name "Net-(IC17-~{CLK0})") (class "Default")
      (node (ref "C92") (pin "2") (pinfunction "2_2") (pintype "passive"))
      (node (ref "IC17") (pin "7") (pinfunction "~{CLK0}_7") (pintype "input"))
      (node (ref "R3") (pin "1") (pinfunction "1_1") (pintype "passive"))
    )
    (net (code "59") (name "Net-(IC17-~{Q1})") (class "Default")
      (node (ref "C109") (pin "2") (pinfunction "2_2") (pintype "passive"))
      (node (ref "IC17") (pin "12") (pinfunction "~{Q1}_12") (pintype "output"))
    )
    (net (code "60") (name "Net-(IC17-~{Q2})") (class "Default")
      (node (ref "C114") (pin "2") (pinfunction "2_2") (pintype "passive"))
      (node (ref "IC17") (pin "14") (pinfunction "~{Q2}_14") (pintype "output"))
    )
    (net (code "61") (name "Net-(IC17-~{Q3})") (class "Default")
      (node (ref "C116") (pin "2") (pinfunction "2_2") (pintype "passive"))
      (node (ref "IC17") (pin "16") (pinfunction "~{Q3}_16") (pintype "output"))
    )
    (net (code "62") (name "Net-(J14-Pad1)") (class "Default")
      (node (ref "J14") (pin "1") (pinfunction "1_1") (pintype "bidirectional"))
      (node (ref "R79") (pin "2") (pinfunction "2_2") (pintype "passive"))
      (node (ref "R87") (pin "2") (pinfunction "2_2") (pintype "passive"))
    )
    (net (code "63") (name "Net-(J14-Pad2)") (class "Default")
      (node (ref "J14") (pin "2") (pinfunction "2_2") (pintype "bidirectional"))
      (node (ref "R76") (pin "1") (pinfunction "1_1") (pintype "passive"))
      (node (ref "R77") (pin "2") (pinfunction "2_2") (pintype "passive"))
    )
    (net (code "64") (name "Net-(OSC1-CLK)") (class "Default")
      (node (ref "OSC1") (pin "3") (pinfunction "CLK_3") (pintype "passive"))
      (node (ref "OSC2") (pin "3") (pinfunction "OUT_3") (pintype "output"))
      (node (ref "R90") (pin "1") (pinfunction "1_1") (pintype "passive"))
    )
    (net (code "65") (name "Net-(OSC2-NC)") (class "Default")
      (node (ref "C100") (pin "2") (pinfunction "2_2") (pintype "passive"))
      (node (ref "OSC2") (pin "1") (pinfunction "NC_1") (pintype "passive"))
      (node (ref "R78") (pin "2") (pinfunction "2_2") (pintype "passive"))
      (node (ref "R87") (pin "1") (pinfunction "1_1") (pintype "passive"))
      (node (ref "R91") (pin "1") (pinfunction "1_1") (pintype "passive"))
      (node (ref "R98") (pin "2") (pinfunction "2_2") (pintype "passive"))
    )
    (net (code "66") (name "Net-(T1-D)") (class "Default")
      (node (ref "L1") (pin "2") (pinfunction "2_2") (pintype "passive"))
      (node (ref "T1") (pin "3") (pinfunction "D_3") (pintype "passive"))
    )
    (net (code "67") (name "Net-(TR3-P)") (class "Default")
      (node (ref "C196") (pin "2") (pinfunction "2_2") (pintype "passive"))
      (node (ref "R113") (pin "1") (pinfunction "1_1") (pintype "passive"))
      (node (ref "TR3") (pin "4") (pinfunction "P_4") (pintype "passive"))
    )
    (net (code "68") (name "P3V3A") (class "Default")
      (node (ref "L13") (pin "2") (pinfunction "2_2") (pintype "passive"))
      (node (ref "L3") (pin "2") (pinfunction "2_2") (pintype "passive"))
      (node (ref "T1") (pin "2") (pinfunction "S_2") (pintype "passive"))
    )
  )
)
